# T4p1_cutout.net
KiCad netlist of a schematic drawn in EAGLE
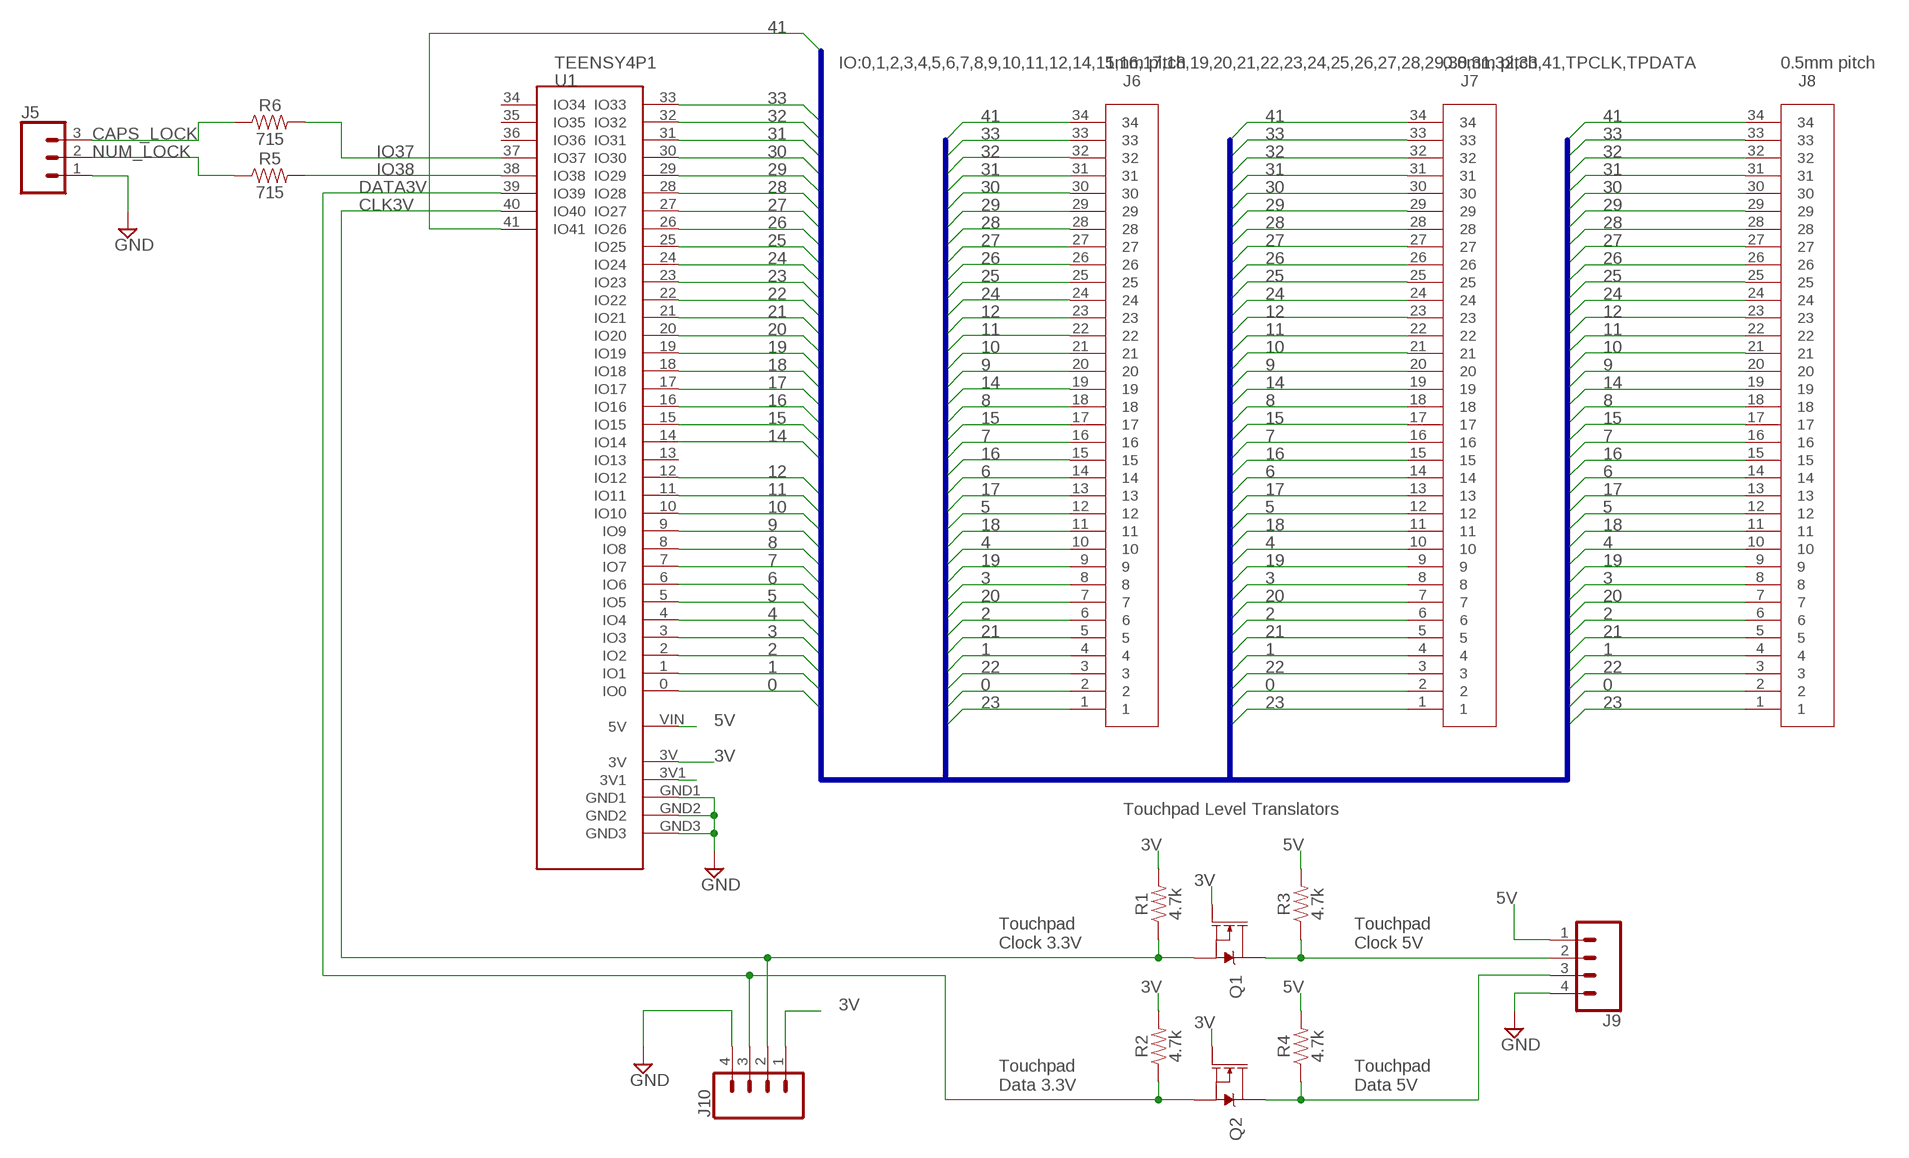
[diagram p0: schematic, sheet 1]

(export (version "E")
  (design (tool "Eeschema 10.0.6"))
  (components
    (comp (ref "J5")
      (value "CONN_031X03_NO_SILK")
      (footprint "eagle-import:1X03_NO_SILK")
      (libsource (lib "eagle-import") (part "CONN_031X03_NO_SILK"))
    )
    (comp (ref "J6")
      (value "FPC34")
      (footprint "eagle-import:FPC34")
      (libsource (lib "eagle-import") (part "FPC34"))
    )
    (comp (ref "J7")
      (value "FPC34_P8MM")
      (footprint "eagle-import:FPC34_P8MM")
      (libsource (lib "eagle-import") (part "FPC34_P8MM"))
    )
    (comp (ref "J8")
      (value "FPC34_P5MM")
      (footprint "eagle-import:FPC34_P5MM")
      (libsource (lib "eagle-import") (part "FPC34_P5MM"))
    )
    (comp (ref "J9")
      (value "CONN_041X04_NO_SILK")
      (footprint "eagle-import:1X04_NO_SILK")
      (libsource (lib "eagle-import") (part "CONN_041X04_NO_SILK"))
    )
    (comp (ref "J10")
      (value "CONN_041X04_NO_SILK")
      (footprint "eagle-import:1X04_NO_SILK")
      (libsource (lib "eagle-import") (part "CONN_041X04_NO_SILK"))
    )
    (comp (ref "Q1")
      (value "220mA/50V/3.5Ω")
      (footprint "eagle-import:SOT23-3")
      (libsource (lib "eagle-import") (part "MOSFET-NCH-BSS138"))
    )
    (comp (ref "Q2")
      (value "220mA/50V/3.5Ω")
      (footprint "eagle-import:SOT23-3")
      (libsource (lib "eagle-import") (part "MOSFET-NCH-BSS138"))
    )
    (comp (ref "R1")
      (value "4.7k")
      (footprint "eagle-import:0603")
      (libsource (lib "eagle-import") (part "4.7KOHM-0603-1/10W-1%"))
    )
    (comp (ref "R2")
      (value "4.7k")
      (footprint "eagle-import:0603")
      (libsource (lib "eagle-import") (part "4.7KOHM-0603-1/10W-1%"))
    )
    (comp (ref "R3")
      (value "4.7k")
      (footprint "eagle-import:0603")
      (libsource (lib "eagle-import") (part "4.7KOHM-0603-1/10W-1%"))
    )
    (comp (ref "R4")
      (value "4.7k")
      (footprint "eagle-import:0603")
      (libsource (lib "eagle-import") (part "4.7KOHM-0603-1/10W-1%"))
    )
    (comp (ref "R5")
      (value "715")
      (footprint "eagle-import:0603")
      (libsource (lib "eagle-import") (part "715OHM-0603-1/10W-1%"))
    )
    (comp (ref "R6")
      (value "715")
      (footprint "eagle-import:0603")
      (libsource (lib "eagle-import") (part "715OHM-0603-1/10W-1%"))
    )
    (comp (ref "U1")
      (value "TEENSY4P1")
      (footprint "eagle-import:TEENSY4P0_CUTOUT")
      (libsource (lib "eagle-import") (part "TEENSY4P1_CUTOUT"))
    )
  )
  (nets
    (net (code "4") (name "/0") (class "Default")
      (node (ref "J6") (pin "2") (pinfunction "2_2") (pintype "bidirectional"))
      (node (ref "J7") (pin "2") (pinfunction "2_2") (pintype "bidirectional"))
      (node (ref "J8") (pin "2") (pinfunction "2_2") (pintype "bidirectional"))
      (node (ref "U1") (pin "0") (pinfunction "IO0_0") (pintype "bidirectional"))
    )
    (net (code "5") (name "/1") (class "Default")
      (node (ref "J6") (pin "4") (pinfunction "4_4") (pintype "bidirectional"))
      (node (ref "J7") (pin "4") (pinfunction "4_4") (pintype "bidirectional"))
      (node (ref "J8") (pin "4") (pinfunction "4_4") (pintype "bidirectional"))
      (node (ref "U1") (pin "1") (pinfunction "IO1_1") (pintype "bidirectional"))
    )
    (net (code "6") (name "/2") (class "Default")
      (node (ref "J6") (pin "6") (pinfunction "6_6") (pintype "bidirectional"))
      (node (ref "J7") (pin "6") (pinfunction "6_6") (pintype "bidirectional"))
      (node (ref "J8") (pin "6") (pinfunction "6_6") (pintype "bidirectional"))
      (node (ref "U1") (pin "2") (pinfunction "IO2_2") (pintype "bidirectional"))
    )
    (net (code "7") (name "/3") (class "Default")
      (node (ref "J6") (pin "8") (pinfunction "8_8") (pintype "bidirectional"))
      (node (ref "J7") (pin "8") (pinfunction "8_8") (pintype "bidirectional"))
      (node (ref "J8") (pin "8") (pinfunction "8_8") (pintype "bidirectional"))
      (node (ref "U1") (pin "3") (pinfunction "IO3_3") (pintype "bidirectional"))
    )
    (net (code "8") (name "/3V") (class "Default")
      (node (ref "J10") (pin "1") (pinfunction "1_1") (pintype "passive"))
      (node (ref "Q1") (pin "1") (pinfunction "G_1") (pintype "bidirectional"))
      (node (ref "Q2") (pin "1") (pinfunction "G_1") (pintype "bidirectional"))
      (node (ref "R1") (pin "2") (pinfunction "2_2") (pintype "passive"))
      (node (ref "R2") (pin "2") (pinfunction "2_2") (pintype "passive"))
      (node (ref "U1") (pin "3V") (pinfunction "3V_3V") (pintype "bidirectional"))
    )
    (net (code "9") (name "/4") (class "Default")
      (node (ref "J6") (pin "10") (pinfunction "10_10") (pintype "bidirectional"))
      (node (ref "J7") (pin "10") (pinfunction "10_10") (pintype "bidirectional"))
      (node (ref "J8") (pin "10") (pinfunction "10_10") (pintype "bidirectional"))
      (node (ref "U1") (pin "4") (pinfunction "IO4_4") (pintype "bidirectional"))
    )
    (net (code "10") (name "/5") (class "Default")
      (node (ref "J6") (pin "12") (pinfunction "12_12") (pintype "bidirectional"))
      (node (ref "J7") (pin "12") (pinfunction "12_12") (pintype "bidirectional"))
      (node (ref "J8") (pin "12") (pinfunction "12_12") (pintype "bidirectional"))
      (node (ref "U1") (pin "5") (pinfunction "IO5_5") (pintype "bidirectional"))
    )
    (net (code "11") (name "/5V") (class "Default")
      (node (ref "J9") (pin "1") (pinfunction "1_1") (pintype "passive"))
      (node (ref "R3") (pin "2") (pinfunction "2_2") (pintype "passive"))
      (node (ref "R4") (pin "2") (pinfunction "2_2") (pintype "passive"))
      (node (ref "U1") (pin "VIN") (pinfunction "5V_VIN") (pintype "bidirectional"))
    )
    (net (code "12") (name "/6") (class "Default")
      (node (ref "J6") (pin "14") (pinfunction "14_14") (pintype "bidirectional"))
      (node (ref "J7") (pin "14") (pinfunction "14_14") (pintype "bidirectional"))
      (node (ref "J8") (pin "14") (pinfunction "14_14") (pintype "bidirectional"))
      (node (ref "U1") (pin "6") (pinfunction "IO6_6") (pintype "bidirectional"))
    )
    (net (code "13") (name "/7") (class "Default")
      (node (ref "J6") (pin "16") (pinfunction "16_16") (pintype "bidirectional"))
      (node (ref "J7") (pin "16") (pinfunction "16_16") (pintype "bidirectional"))
      (node (ref "J8") (pin "16") (pinfunction "16_16") (pintype "bidirectional"))
      (node (ref "U1") (pin "7") (pinfunction "IO7_7") (pintype "bidirectional"))
    )
    (net (code "14") (name "/8") (class "Default")
      (node (ref "J6") (pin "18") (pinfunction "18_18") (pintype "bidirectional"))
      (node (ref "J7") (pin "18") (pinfunction "18_18") (pintype "bidirectional"))
      (node (ref "J8") (pin "18") (pinfunction "18_18") (pintype "bidirectional"))
      (node (ref "U1") (pin "8") (pinfunction "IO8_8") (pintype "bidirectional"))
    )
    (net (code "15") (name "/9") (class "Default")
      (node (ref "J6") (pin "20") (pinfunction "20_20") (pintype "bidirectional"))
      (node (ref "J7") (pin "20") (pinfunction "20_20") (pintype "bidirectional"))
      (node (ref "J8") (pin "20") (pinfunction "20_20") (pintype "bidirectional"))
      (node (ref "U1") (pin "9") (pinfunction "IO9_9") (pintype "bidirectional"))
    )
    (net (code "16") (name "/10") (class "Default")
      (node (ref "J6") (pin "21") (pinfunction "21_21") (pintype "bidirectional"))
      (node (ref "J7") (pin "21") (pinfunction "21_21") (pintype "bidirectional"))
      (node (ref "J8") (pin "21") (pinfunction "21_21") (pintype "bidirectional"))
      (node (ref "U1") (pin "10") (pinfunction "IO10_10") (pintype "bidirectional"))
    )
    (net (code "17") (name "/11") (class "Default")
      (node (ref "J6") (pin "22") (pinfunction "22_22") (pintype "bidirectional"))
      (node (ref "J7") (pin "22") (pinfunction "22_22") (pintype "bidirectional"))
      (node (ref "J8") (pin "22") (pinfunction "22_22") (pintype "bidirectional"))
      (node (ref "U1") (pin "11") (pinfunction "IO11_11") (pintype "bidirectional"))
    )
    (net (code "18") (name "/12") (class "Default")
      (node (ref "J6") (pin "23") (pinfunction "23_23") (pintype "bidirectional"))
      (node (ref "J7") (pin "23") (pinfunction "23_23") (pintype "bidirectional"))
      (node (ref "J8") (pin "23") (pinfunction "23_23") (pintype "bidirectional"))
      (node (ref "U1") (pin "12") (pinfunction "IO12_12") (pintype "bidirectional"))
    )
    (net (code "19") (name "/14") (class "Default")
      (node (ref "J6") (pin "19") (pinfunction "19_19") (pintype "bidirectional"))
      (node (ref "J7") (pin "19") (pinfunction "19_19") (pintype "bidirectional"))
      (node (ref "J8") (pin "19") (pinfunction "19_19") (pintype "bidirectional"))
      (node (ref "U1") (pin "14") (pinfunction "IO14_14") (pintype "bidirectional"))
    )
    (net (code "20") (name "/15") (class "Default")
      (node (ref "J6") (pin "17") (pinfunction "17_17") (pintype "bidirectional"))
      (node (ref "J7") (pin "17") (pinfunction "17_17") (pintype "bidirectional"))
      (node (ref "J8") (pin "17") (pinfunction "17_17") (pintype "bidirectional"))
      (node (ref "U1") (pin "15") (pinfunction "IO15_15") (pintype "bidirectional"))
    )
    (net (code "21") (name "/16") (class "Default")
      (node (ref "J6") (pin "15") (pinfunction "15_15") (pintype "bidirectional"))
      (node (ref "J7") (pin "15") (pinfunction "15_15") (pintype "bidirectional"))
      (node (ref "J8") (pin "15") (pinfunction "15_15") (pintype "bidirectional"))
      (node (ref "U1") (pin "16") (pinfunction "IO16_16") (pintype "bidirectional"))
    )
    (net (code "22") (name "/17") (class "Default")
      (node (ref "J6") (pin "13") (pinfunction "13_13") (pintype "bidirectional"))
      (node (ref "J7") (pin "13") (pinfunction "13_13") (pintype "bidirectional"))
      (node (ref "J8") (pin "13") (pinfunction "13_13") (pintype "bidirectional"))
      (node (ref "U1") (pin "17") (pinfunction "IO17_17") (pintype "bidirectional"))
    )
    (net (code "23") (name "/18") (class "Default")
      (node (ref "J6") (pin "11") (pinfunction "11_11") (pintype "bidirectional"))
      (node (ref "J7") (pin "11") (pinfunction "11_11") (pintype "bidirectional"))
      (node (ref "J8") (pin "11") (pinfunction "11_11") (pintype "bidirectional"))
      (node (ref "U1") (pin "18") (pinfunction "IO18_18") (pintype "bidirectional"))
    )
    (net (code "24") (name "/19") (class "Default")
      (node (ref "J6") (pin "9") (pinfunction "9_9") (pintype "bidirectional"))
      (node (ref "J7") (pin "9") (pinfunction "9_9") (pintype "bidirectional"))
      (node (ref "J8") (pin "9") (pinfunction "9_9") (pintype "bidirectional"))
      (node (ref "U1") (pin "19") (pinfunction "IO19_19") (pintype "bidirectional"))
    )
    (net (code "25") (name "/20") (class "Default")
      (node (ref "J6") (pin "7") (pinfunction "7_7") (pintype "bidirectional"))
      (node (ref "J7") (pin "7") (pinfunction "7_7") (pintype "bidirectional"))
      (node (ref "J8") (pin "7") (pinfunction "7_7") (pintype "bidirectional"))
      (node (ref "U1") (pin "20") (pinfunction "IO20_20") (pintype "bidirectional"))
    )
    (net (code "26") (name "/21") (class "Default")
      (node (ref "J6") (pin "5") (pinfunction "5_5") (pintype "bidirectional"))
      (node (ref "J7") (pin "5") (pinfunction "5_5") (pintype "bidirectional"))
      (node (ref "J8") (pin "5") (pinfunction "5_5") (pintype "bidirectional"))
      (node (ref "U1") (pin "21") (pinfunction "IO21_21") (pintype "bidirectional"))
    )
    (net (code "27") (name "/22") (class "Default")
      (node (ref "J6") (pin "3") (pinfunction "3_3") (pintype "bidirectional"))
      (node (ref "J7") (pin "3") (pinfunction "3_3") (pintype "bidirectional"))
      (node (ref "J8") (pin "3") (pinfunction "3_3") (pintype "bidirectional"))
      (node (ref "U1") (pin "22") (pinfunction "IO22_22") (pintype "bidirectional"))
    )
    (net (code "28") (name "/23") (class "Default")
      (node (ref "J6") (pin "1") (pinfunction "1_1") (pintype "bidirectional"))
      (node (ref "J7") (pin "1") (pinfunction "1_1") (pintype "bidirectional"))
      (node (ref "J8") (pin "1") (pinfunction "1_1") (pintype "bidirectional"))
      (node (ref "U1") (pin "23") (pinfunction "IO23_23") (pintype "bidirectional"))
    )
    (net (code "29") (name "/24") (class "Default")
      (node (ref "J6") (pin "24") (pinfunction "24_24") (pintype "bidirectional"))
      (node (ref "J7") (pin "24") (pinfunction "24_24") (pintype "bidirectional"))
      (node (ref "J8") (pin "24") (pinfunction "24_24") (pintype "bidirectional"))
      (node (ref "U1") (pin "24") (pinfunction "IO24_24") (pintype "bidirectional"))
    )
    (net (code "30") (name "/25") (class "Default")
      (node (ref "J6") (pin "25") (pinfunction "25_25") (pintype "bidirectional"))
      (node (ref "J7") (pin "25") (pinfunction "25_25") (pintype "bidirectional"))
      (node (ref "J8") (pin "25") (pinfunction "25_25") (pintype "bidirectional"))
      (node (ref "U1") (pin "25") (pinfunction "IO25_25") (pintype "bidirectional"))
    )
    (net (code "31") (name "/26") (class "Default")
      (node (ref "J6") (pin "26") (pinfunction "26_26") (pintype "bidirectional"))
      (node (ref "J7") (pin "26") (pinfunction "26_26") (pintype "bidirectional"))
      (node (ref "J8") (pin "26") (pinfunction "26_26") (pintype "bidirectional"))
      (node (ref "U1") (pin "26") (pinfunction "IO26_26") (pintype "bidirectional"))
    )
    (net (code "32") (name "/27") (class "Default")
      (node (ref "J6") (pin "27") (pinfunction "27_27") (pintype "bidirectional"))
      (node (ref "J7") (pin "27") (pinfunction "27_27") (pintype "bidirectional"))
      (node (ref "J8") (pin "27") (pinfunction "27_27") (pintype "bidirectional"))
      (node (ref "U1") (pin "27") (pinfunction "IO27_27") (pintype "bidirectional"))
    )
    (net (code "33") (name "/28") (class "Default")
      (node (ref "J6") (pin "28") (pinfunction "28_28") (pintype "bidirectional"))
      (node (ref "J7") (pin "28") (pinfunction "28_28") (pintype "bidirectional"))
      (node (ref "J8") (pin "28") (pinfunction "28_28") (pintype "bidirectional"))
      (node (ref "U1") (pin "28") (pinfunction "IO28_28") (pintype "bidirectional"))
    )
    (net (code "34") (name "/29") (class "Default")
      (node (ref "J6") (pin "29") (pinfunction "29_29") (pintype "bidirectional"))
      (node (ref "J7") (pin "29") (pinfunction "29_29") (pintype "bidirectional"))
      (node (ref "J8") (pin "29") (pinfunction "29_29") (pintype "bidirectional"))
      (node (ref "U1") (pin "29") (pinfunction "IO29_29") (pintype "bidirectional"))
    )
    (net (code "35") (name "/30") (class "Default")
      (node (ref "J6") (pin "30") (pinfunction "30_30") (pintype "bidirectional"))
      (node (ref "J7") (pin "30") (pinfunction "30_30") (pintype "bidirectional"))
      (node (ref "J8") (pin "30") (pinfunction "30_30") (pintype "bidirectional"))
      (node (ref "U1") (pin "30") (pinfunction "IO30_30") (pintype "bidirectional"))
    )
    (net (code "36") (name "/31") (class "Default")
      (node (ref "J6") (pin "31") (pinfunction "31_31") (pintype "bidirectional"))
      (node (ref "J7") (pin "31") (pinfunction "31_31") (pintype "bidirectional"))
      (node (ref "J8") (pin "31") (pinfunction "31_31") (pintype "bidirectional"))
      (node (ref "U1") (pin "31") (pinfunction "IO31_31") (pintype "bidirectional"))
    )
    (net (code "37") (name "/32") (class "Default")
      (node (ref "J6") (pin "32") (pinfunction "32_32") (pintype "bidirectional"))
      (node (ref "J7") (pin "32") (pinfunction "32_32") (pintype "bidirectional"))
      (node (ref "J8") (pin "32") (pinfunction "32_32") (pintype "bidirectional"))
      (node (ref "U1") (pin "32") (pinfunction "IO32_32") (pintype "bidirectional"))
    )
    (net (code "38") (name "/33") (class "Default")
      (node (ref "J6") (pin "33") (pinfunction "33_33") (pintype "bidirectional"))
      (node (ref "J7") (pin "33") (pinfunction "33_33") (pintype "bidirectional"))
      (node (ref "J8") (pin "33") (pinfunction "33_33") (pintype "bidirectional"))
      (node (ref "U1") (pin "33") (pinfunction "IO33_33") (pintype "bidirectional"))
    )
    (net (code "39") (name "/41") (class "Default")
      (node (ref "J6") (pin "34") (pinfunction "34_34") (pintype "bidirectional"))
      (node (ref "J7") (pin "34") (pinfunction "34_34") (pintype "bidirectional"))
      (node (ref "J8") (pin "34") (pinfunction "34_34") (pintype "bidirectional"))
      (node (ref "U1") (pin "41") (pinfunction "IO41_41") (pintype "bidirectional"))
    )
    (net (code "40") (name "/CAPS_LOCK") (class "Default")
      (node (ref "J5") (pin "3") (pinfunction "3_3") (pintype "passive"))
      (node (ref "R6") (pin "1") (pinfunction "1_1") (pintype "passive"))
    )
    (net (code "41") (name "/CLK3V") (class "Default")
      (node (ref "J10") (pin "2") (pinfunction "2_2") (pintype "passive"))
      (node (ref "Q1") (pin "2") (pinfunction "S_2") (pintype "bidirectional"))
      (node (ref "R1") (pin "1") (pinfunction "1_1") (pintype "passive"))
      (node (ref "U1") (pin "40") (pinfunction "IO40_40") (pintype "bidirectional"))
    )
    (net (code "42") (name "/DATA3V") (class "Default")
      (node (ref "J10") (pin "3") (pinfunction "3_3") (pintype "passive"))
      (node (ref "Q2") (pin "2") (pinfunction "S_2") (pintype "bidirectional"))
      (node (ref "R2") (pin "1") (pinfunction "1_1") (pintype "passive"))
      (node (ref "U1") (pin "39") (pinfunction "IO39_39") (pintype "bidirectional"))
    )
    (net (code "43") (name "/IO37") (class "Default")
      (node (ref "R6") (pin "2") (pinfunction "2_2") (pintype "passive"))
      (node (ref "U1") (pin "37") (pinfunction "IO37_37") (pintype "bidirectional"))
    )
    (net (code "44") (name "/IO38") (class "Default")
      (node (ref "R5") (pin "2") (pinfunction "2_2") (pintype "passive"))
      (node (ref "U1") (pin "38") (pinfunction "IO38_38") (pintype "bidirectional"))
    )
    (net (code "45") (name "/NUM_LOCK") (class "Default")
      (node (ref "J5") (pin "2") (pinfunction "2_2") (pintype "passive"))
      (node (ref "R5") (pin "1") (pinfunction "1_1") (pintype "passive"))
    )
    (net (code "47") (name "GND") (class "Default")
      (node (ref "J10") (pin "4") (pinfunction "4_4") (pintype "passive"))
      (node (ref "J5") (pin "1") (pinfunction "1_1") (pintype "passive"))
      (node (ref "J9") (pin "4") (pinfunction "4_4") (pintype "passive"))
      (node (ref "U1") (pin "GND1") (pinfunction "GND1_GND1") (pintype "bidirectional"))
      (node (ref "U1") (pin "GND2") (pinfunction "GND2_GND2") (pintype "bidirectional"))
      (node (ref "U1") (pin "GND3") (pinfunction "GND3_GND3") (pintype "bidirectional"))
    )
    (net (code "48") (name "Net-(Q1-D)") (class "Default")
      (node (ref "J9") (pin "2") (pinfunction "2_2") (pintype "passive"))
      (node (ref "Q1") (pin "3") (pinfunction "D_3") (pintype "bidirectional"))
      (node (ref "R3") (pin "1") (pinfunction "1_1") (pintype "passive"))
    )
    (net (code "49") (name "Net-(Q2-D)") (class "Default")
      (node (ref "J9") (pin "3") (pinfunction "3_3") (pintype "passive"))
      (node (ref "Q2") (pin "3") (pinfunction "D_3") (pintype "bidirectional"))
      (node (ref "R4") (pin "1") (pinfunction "1_1") (pintype "passive"))
    )
    (net (code "50") (name "unconnected-(U1-IO13-Pad13)") (class "Default")
      (node (ref "U1") (pin "13") (pinfunction "IO13_13") (pintype "bidirectional"))
    )
    (net (code "51") (name "unconnected-(U1-IO34-Pad34)") (class "Default")
      (node (ref "U1") (pin "34") (pinfunction "IO34_34") (pintype "bidirectional"))
    )
    (net (code "52") (name "unconnected-(U1-IO35-Pad35)") (class "Default")
      (node (ref "U1") (pin "35") (pinfunction "IO35_35") (pintype "bidirectional"))
    )
    (net (code "53") (name "unconnected-(U1-IO36-Pad36)") (class "Default")
      (node (ref "U1") (pin "36") (pinfunction "IO36_36") (pintype "bidirectional"))
    )
    (net (code "54") (name "unconnected-(U1-Pad3V1)") (class "Default")
      (node (ref "U1") (pin "3V1") (pinfunction "3V1_3V1") (pintype "bidirectional"))
    )
  )
)
